# STM32F103C8T6_Subentry.net
KiCad netlist of a schematic drawn in Altium Designer
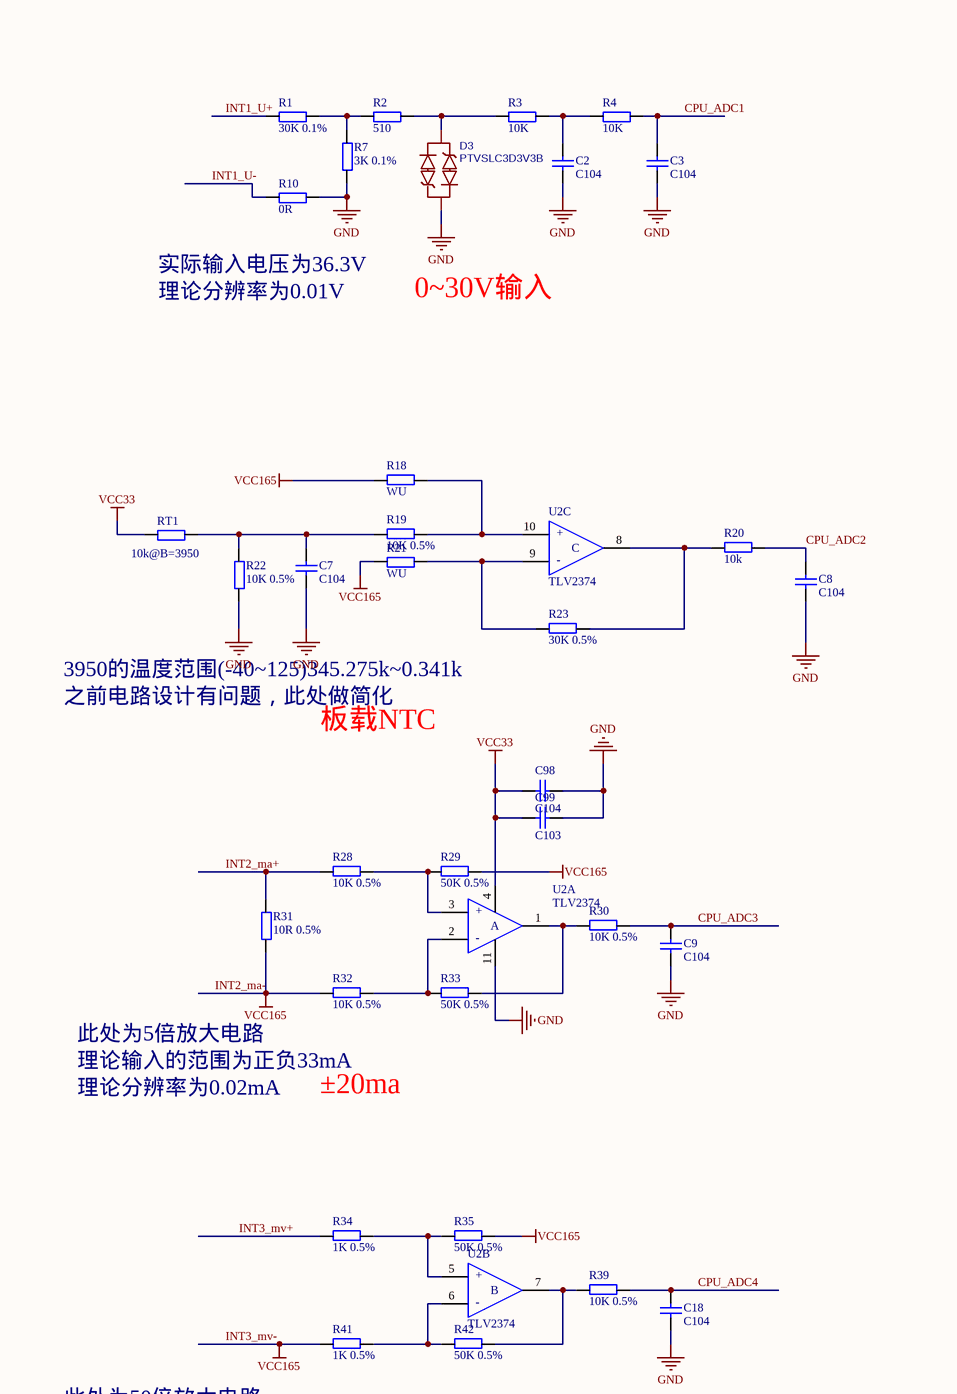
[diagram p0: STM32F103C8T6_Subentry.SchDoc, top left]
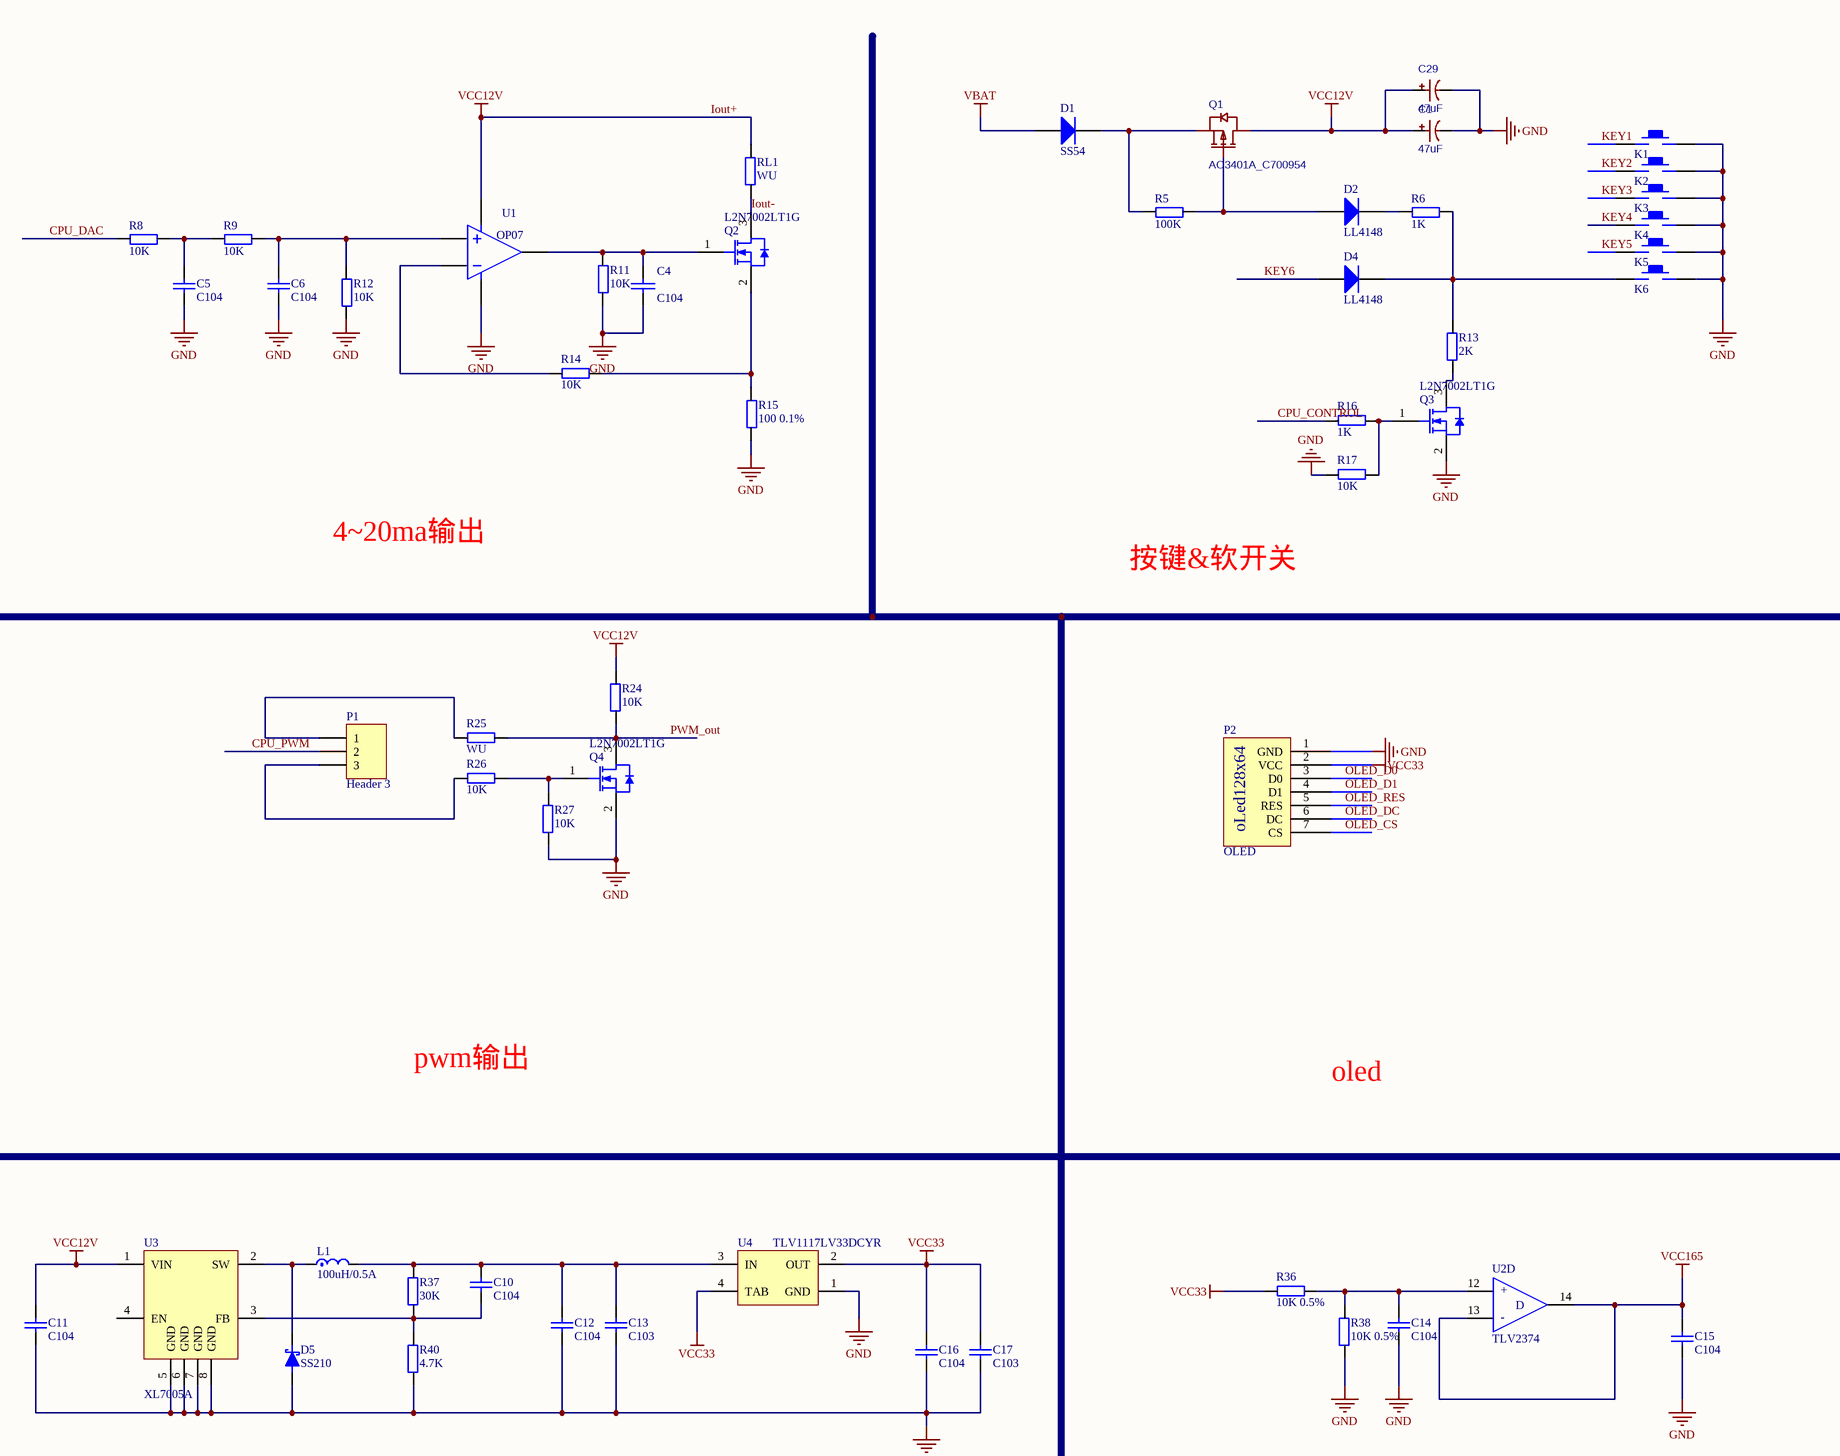
[diagram p1: STM32F103C8T6_Subentry.SchDoc, top right]
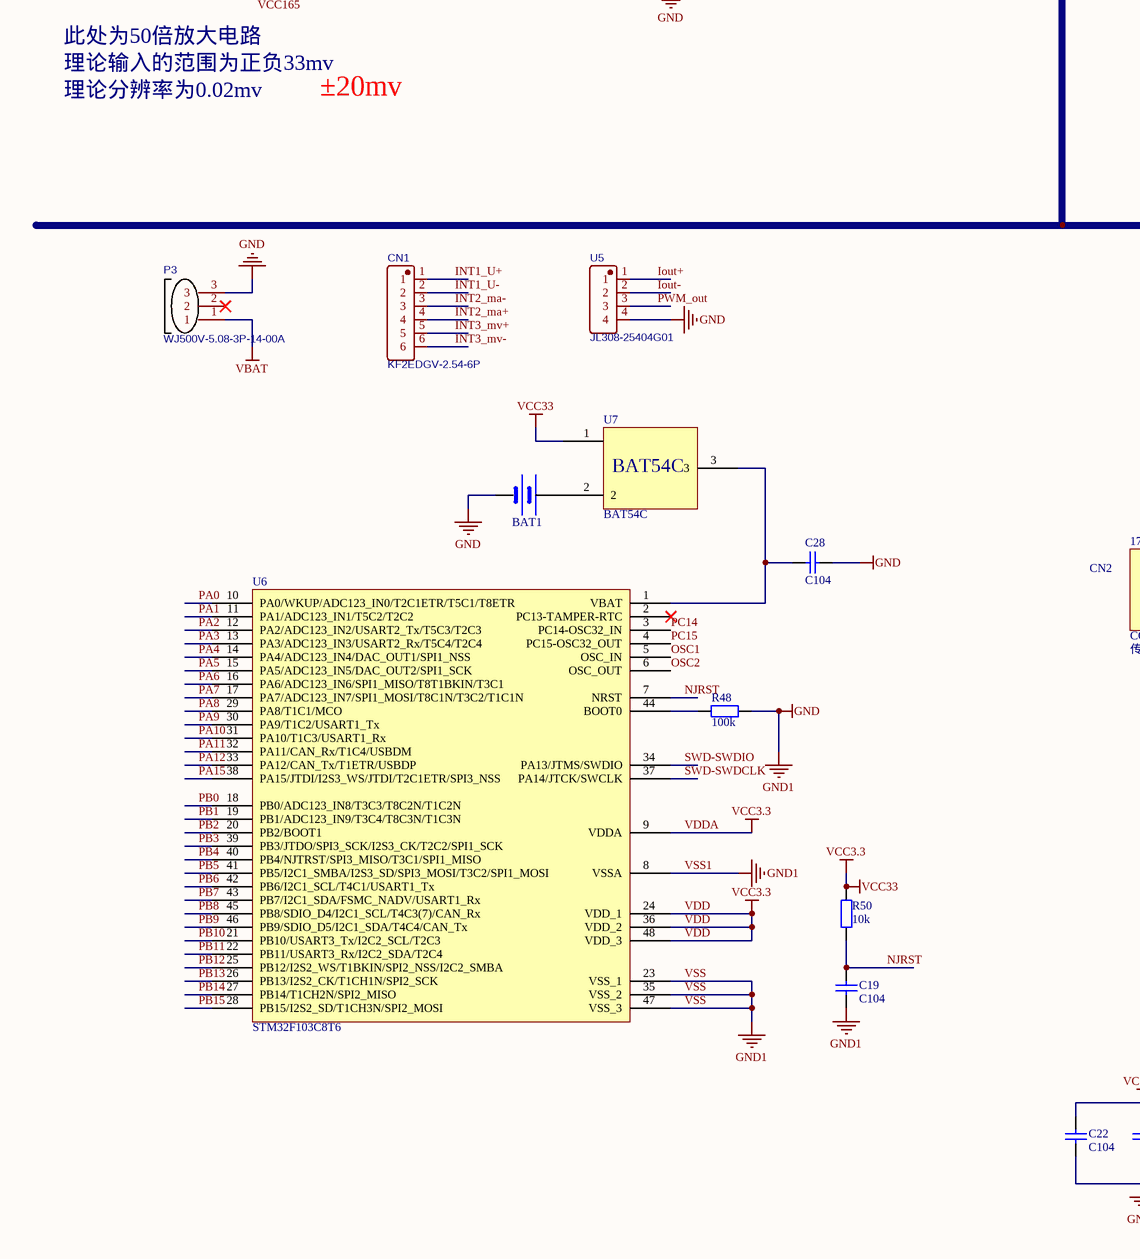
[diagram p2: STM32F103C8T6_Subentry.SchDoc, bottom left]
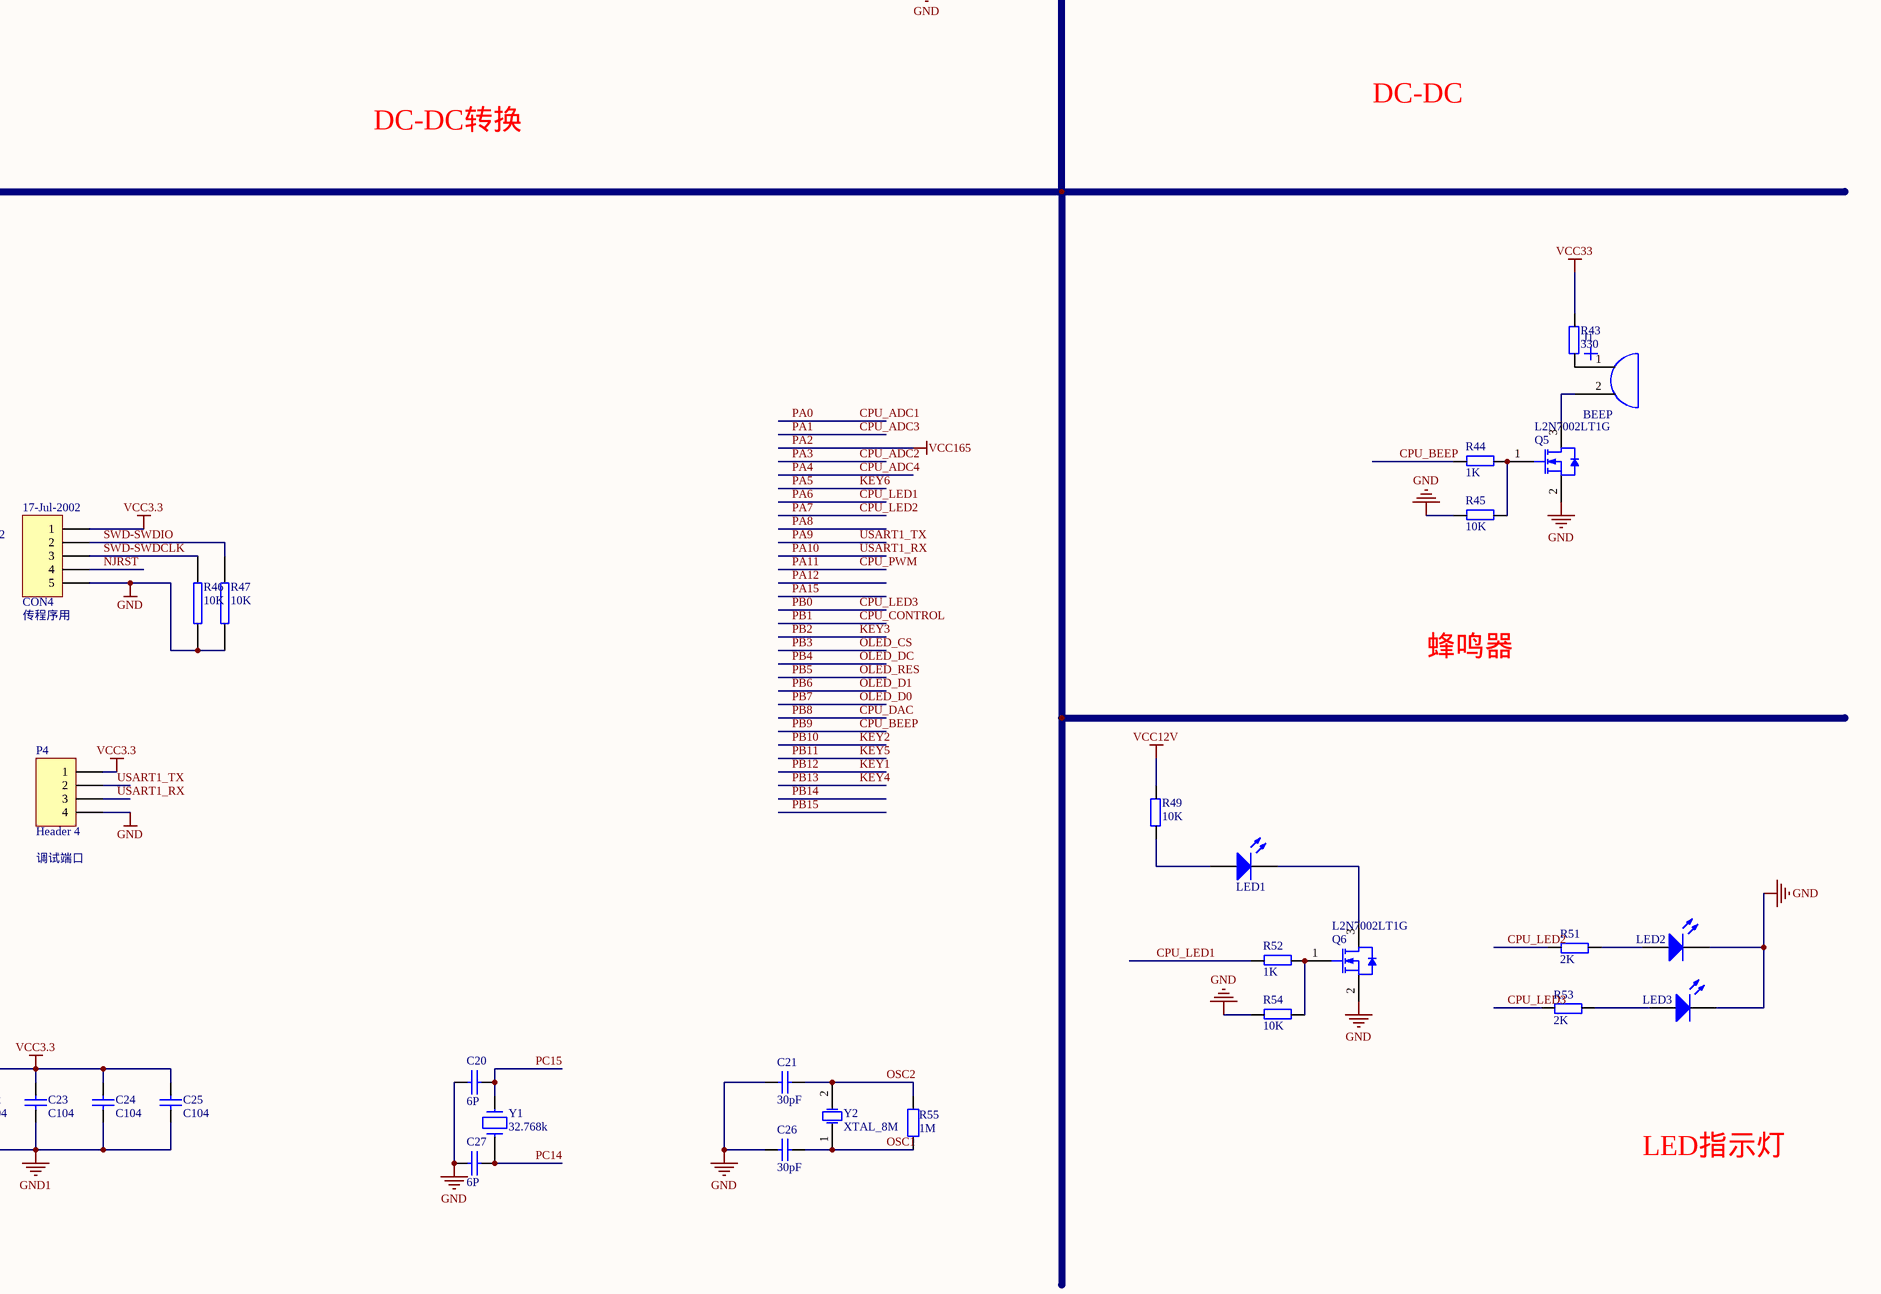
[diagram p3: STM32F103C8T6_Subentry.SchDoc, bottom right]

(export (version "E")
  (design (tool "Eeschema 10.0.6"))
  (components
    (comp (ref "BAT1") (value "BATT") (footprint "CR1220") (libsource (lib "STM32F429_F746") (part "BAT")))
    (comp (ref "C1")
      (value "47uF")
      (footprint "CAP-TH_BD5.0-P2.00-D0.8-FD")
      (fields
        (field (name "BOM_MANUFACTURER PART") "35YXJ47M5X11")
        (field (name "BOM_SUPPLIER PART") "C88761")
      )
      (libsource (lib "STM32F103C8T6_Subentry") (part "47uF"))
    )
    (comp (ref "C2")
      (value "C104")
      (footprint "AD_NEW:C0805")
      (description "Capacitor")
      (fields (field (name "PUBLISHER") "Altium Limited"))
      (libsource (lib "Miscellaneous Devices") (part "Cap"))
    )
    (comp (ref "C3")
      (value "C104")
      (footprint "AD_NEW:C0805")
      (description "Capacitor")
      (fields (field (name "PUBLISHER") "Altium Limited"))
      (libsource (lib "Miscellaneous Devices") (part "Cap"))
    )
    (comp (ref "C4")
      (value "C104")
      (footprint "AD_NEW:C0805")
      (description "Capacitor")
      (libsource (lib "*") (part "CAP"))
    )
    (comp (ref "C5")
      (value "C104")
      (footprint "AD_NEW:C0805")
      (description "Capacitor")
      (fields (field (name "PUBLISHER") "Altium Limited"))
      (libsource (lib "Miscellaneous Devices") (part "Cap"))
    )
    (comp (ref "C6")
      (value "C104")
      (footprint "AD_NEW:C0805")
      (description "Capacitor")
      (fields (field (name "PUBLISHER") "Altium Limited"))
      (libsource (lib "Miscellaneous Devices") (part "Cap"))
    )
    (comp (ref "C7")
      (value "C104")
      (footprint "AD_NEW:C0805")
      (description "Capacitor")
      (fields (field (name "PUBLISHER") "Altium Limited"))
      (libsource (lib "Miscellaneous Devices") (part "Cap"))
    )
    (comp (ref "C8")
      (value "C104")
      (footprint "AD_NEW:C0805")
      (description "Capacitor")
      (fields (field (name "PUBLISHER") "Altium Limited"))
      (libsource (lib "Miscellaneous Devices") (part "Cap"))
    )
    (comp (ref "C9")
      (value "C104")
      (footprint "AD_NEW:C0805")
      (description "Capacitor")
      (fields (field (name "PUBLISHER") "Altium Limited"))
      (libsource (lib "Miscellaneous Devices") (part "Cap"))
    )
    (comp (ref "C10")
      (value "C104")
      (footprint "AD_NEW:C0805")
      (description "Capacitor")
      (fields (field (name "PUBLISHER") "Altium Limited"))
      (libsource (lib "Miscellaneous Devices") (part "Cap"))
    )
    (comp (ref "C11")
      (value "C104")
      (footprint "AD_NEW:C0805")
      (description "Capacitor")
      (fields (field (name "PUBLISHER") "Altium Limited"))
      (libsource (lib "Miscellaneous Devices") (part "Cap"))
    )
    (comp (ref "C12")
      (value "C104")
      (footprint "AD_NEW:C0805")
      (description "Capacitor")
      (fields (field (name "PUBLISHER") "Altium Limited"))
      (libsource (lib "Miscellaneous Devices") (part "Cap"))
    )
    (comp (ref "C13")
      (value "C103")
      (footprint "AD_NEW:C0805")
      (description "Capacitor")
      (fields (field (name "PUBLISHER") "Altium Limited"))
      (libsource (lib "Miscellaneous Devices") (part "Cap"))
    )
    (comp (ref "C14")
      (value "C104")
      (footprint "AD_NEW:C0805")
      (description "Capacitor")
      (fields (field (name "PUBLISHER") "Altium Limited"))
      (libsource (lib "Miscellaneous Devices") (part "Cap"))
    )
    (comp (ref "C15")
      (value "C104")
      (footprint "AD_NEW:C0805")
      (description "Capacitor")
      (fields (field (name "PUBLISHER") "Altium Limited"))
      (libsource (lib "Miscellaneous Devices") (part "Cap"))
    )
    (comp (ref "C16")
      (value "C104")
      (footprint "AD_NEW:C0805")
      (description "Capacitor")
      (fields (field (name "PUBLISHER") "Altium Limited"))
      (libsource (lib "Miscellaneous Devices") (part "Cap"))
    )
    (comp (ref "C17")
      (value "C103")
      (footprint "AD_NEW:C0805")
      (description "Capacitor")
      (fields (field (name "PUBLISHER") "Altium Limited"))
      (libsource (lib "Miscellaneous Devices") (part "Cap"))
    )
    (comp (ref "C18")
      (value "C104")
      (footprint "AD_NEW:C0805")
      (description "Capacitor")
      (fields (field (name "PUBLISHER") "Altium Limited"))
      (libsource (lib "Miscellaneous Devices") (part "Cap"))
    )
    (comp (ref "C19")
      (value "C104")
      (footprint "AD_NEW:C0805")
      (description "Capacitor")
      (fields (field (name "PUBLISHER") "Altium Limited"))
      (libsource (lib "Miscellaneous Devices") (part "Cap"))
    )
    (comp (ref "C20")
      (value "6P")
      (footprint "AD_NEW:C0805")
      (description "Capacitor")
      (libsource (lib "") (part "CAP_1"))
    )
    (comp (ref "C21")
      (value "30pF")
      (footprint "AD_NEW:C0805")
      (description "Capacitor")
      (fields (field (name "PUBLISHER") "Altium Limited"))
      (libsource (lib "Miscellaneous Devices") (part "Cap"))
    )
    (comp (ref "C22")
      (value "C104")
      (footprint "AD_NEW:C0805")
      (description "Capacitor")
      (fields (field (name "PUBLISHER") "Altium Limited"))
      (libsource (lib "Miscellaneous Devices") (part "Cap"))
    )
    (comp (ref "C23")
      (value "C104")
      (footprint "AD_NEW:C0805")
      (description "Capacitor")
      (fields (field (name "PUBLISHER") "Altium Limited"))
      (libsource (lib "Miscellaneous Devices") (part "Cap"))
    )
    (comp (ref "C24")
      (value "C104")
      (footprint "AD_NEW:C0805")
      (description "Capacitor")
      (fields (field (name "PUBLISHER") "Altium Limited"))
      (libsource (lib "Miscellaneous Devices") (part "Cap"))
    )
    (comp (ref "C25")
      (value "C104")
      (footprint "AD_NEW:C0805")
      (description "Capacitor")
      (fields (field (name "PUBLISHER") "Altium Limited"))
      (libsource (lib "Miscellaneous Devices") (part "Cap"))
    )
    (comp (ref "C26")
      (value "30pF")
      (footprint "AD_NEW:C0805")
      (description "Capacitor")
      (fields (field (name "PUBLISHER") "Altium Limited"))
      (libsource (lib "Miscellaneous Devices") (part "Cap"))
    )
    (comp (ref "C27")
      (value "6P")
      (footprint "AD_NEW:C0805")
      (description "Capacitor")
      (libsource (lib "") (part "CAP_1"))
    )
    (comp (ref "C28")
      (value "C104")
      (footprint "AD_NEW:C0805")
      (description "Capacitor")
      (fields (field (name "PUBLISHER") "Altium Limited"))
      (libsource (lib "Miscellaneous Devices") (part "Cap"))
    )
    (comp (ref "C29")
      (value "47uF")
      (footprint "CAP-TH_BD5.0-P2.00-D0.8-FD")
      (fields
        (field (name "BOM_MANUFACTURER PART") "35YXJ47M5X11")
        (field (name "BOM_SUPPLIER PART") "C88761")
      )
      (libsource (lib "STM32F103C8T6_Subentry") (part "47uF"))
    )
    (comp (ref "C98")
      (value "C104")
      (footprint "AD_NEW:C0805")
      (description "Capacitor")
      (fields (field (name "PUBLISHER") "Altium Limited"))
      (libsource (lib "Miscellaneous Devices") (part "Cap"))
    )
    (comp (ref "C99")
      (value "C103")
      (footprint "AD_NEW:C0805")
      (description "Capacitor")
      (fields (field (name "PUBLISHER") "Altium Limited"))
      (libsource (lib "Miscellaneous Devices") (part "Cap"))
    )
    (comp (ref "CN1")
      (value "KF2EDGV-2.54-6P")
      (footprint "CONN-TH_6P-P2.54_KF2EDGV-2.54-6P")
      (fields (field (name "BOM_SUPPLIER PART") "C577589") (field (name "CONTRIBUTOR") "LCSC"))
      (libsource (lib "STM32F103C8T6_Subentry") (part "KF2EDGV-2.54-6P"))
    )
    (comp (ref "CN2")
      (value "CON4")
      (footprint "HDR1X5")
      (description "Header, 5-Pin")
      (fields (field (name "LATESTREVISIONDATE") "17-Jul-2002") (field (name "PUBLISHER") "Altium Limited"))
      (libsource (lib "通用接插头符号") (part "Header 5"))
    )
    (comp (ref "D1")
      (value "SS54")
      (footprint "GNN:DIODE-SMB")
      (description "3 Amp General Purpose Rectifier")
      (fields (field (name "PUBLISHER") "Altium Limited"))
      (libsource (lib "Miscellaneous Devices") (part "Diode 1N5404"))
    )
    (comp (ref "D2")
      (value "LL4148")
      (footprint "LL-34_L3.5-W1.5-RD")
      (description "Default Diode")
      (fields (field (name "PUBLISHER") "Altium Limited"))
      (libsource (lib "Miscellaneous Devices") (part "Diode"))
    )
    (comp (ref "D3")
      (value "PTVSLC3D3V3B")
      (footprint "SOD-323_L1.8-W1.3-LS2.5-BI")
      (fields (field (name "BOM_SUPPLIER PART") "C246774") (field (name "CONTRIBUTOR") "LCSC"))
      (libsource (lib "STM32F103C8T6_Subentry") (part "PTVSLC3D3V3B"))
    )
    (comp (ref "D4")
      (value "LL4148")
      (footprint "LL-34_L3.5-W1.5-RD")
      (description "Default Diode")
      (fields (field (name "PUBLISHER") "Altium Limited"))
      (libsource (lib "Miscellaneous Devices") (part "Diode"))
    )
    (comp (ref "D5") (value "SS210") (footprint "SMA") (libsource (lib "BB4805S") (part "DIODE SCHOTTKY")))
    (comp (ref "J1")
      (value "BEEP")
      (footprint "GNN:Beep")
      (description "蜂鸣器")
      (libsource (lib "GNN") (part "BEEP"))
    )
    (comp (ref "K1")
      (value "KEY_M")
      (footprint "K0.25")
      (libsource (lib "WarShip V3 STM32103封装库") (part "KEY_M"))
    )
    (comp (ref "K2")
      (value "KEY_M")
      (footprint "K0.25")
      (libsource (lib "WarShip V3 STM32103封装库") (part "KEY_M"))
    )
    (comp (ref "K3")
      (value "KEY_M")
      (footprint "K0.25")
      (libsource (lib "WarShip V3 STM32103封装库") (part "KEY_M"))
    )
    (comp (ref "K4")
      (value "KEY_M")
      (footprint "K0.25")
      (libsource (lib "WarShip V3 STM32103封装库") (part "KEY_M"))
    )
    (comp (ref "K5")
      (value "KEY_M")
      (footprint "K0.25")
      (libsource (lib "WarShip V3 STM32103封装库") (part "KEY_M"))
    )
    (comp (ref "K6") (value "KEY_M") (footprint "K0.25") (libsource (lib "") (part "KEY_M_1")))
    (comp (ref "L1") (value "100uH/0.5A") (footprint "L0630") (libsource (lib "BB4805S") (part "INDUTOR")))
    (comp (ref "LED1")
      (value "LED")
      (footprint "LED-0603 - duplicate")
      (description "白色贴片指示灯")
      (fields (field (name "PUBLISHER") "Altium Limited"))
      (libsource (lib "MySchlib1") (part "LED"))
    )
    (comp (ref "LED2")
      (value "LED")
      (footprint "LED-0603 - duplicate")
      (description "白色贴片指示灯")
      (fields (field (name "PUBLISHER") "Altium Limited"))
      (libsource (lib "MySchlib1") (part "LED"))
    )
    (comp (ref "LED3")
      (value "LED")
      (footprint "LED-0603 - duplicate")
      (description "白色贴片指示灯")
      (fields (field (name "PUBLISHER") "Altium Limited"))
      (libsource (lib "MySchlib1") (part "LED"))
    )
    (comp (ref "P1")
      (value "Header 3")
      (footprint "HDR1X3")
      (description "Header, 3-Pin")
      (fields (field (name "PUBLISHER") "Altium Limited"))
      (libsource (lib "Miscellaneous Connectors") (part "Header 3"))
    )
    (comp (ref "P2") (value "OLED") (footprint "OLED") (libsource (lib "Schlib1") (part "OLED")))
    (comp (ref "P3")
      (value "WJ500V-5.08-3P-14-00A")
      (footprint "CONN-TH_3P-P5.00_WJ500V-5.08-3P")
      (fields (field (name "BOM_SUPPLIER PART") "C72334"))
      (libsource (lib "STM32F103C8T6_Subentry") (part "WJ500V-5.08-3P-14-00A"))
    )
    (comp (ref "P4")
      (value "Header 4")
      (footprint "HDR1X4")
      (description "Header, 4-Pin")
      (fields (field (name "PUBLISHER") "Altium Limited"))
      (libsource (lib "Miscellaneous Connectors") (part "Header 4"))
    )
    (comp (ref "Q1")
      (value "AO3401A_C700954")
      (footprint "SOT-23")
      (fields
        (field (name "BOM_SUPPLIER PART") "C700954")
        (field (name "BOM_MANUFACTURER PART") "AO3401A")
        (field (name "CONTRIBUTOR") "LCSC")
      )
      (libsource (lib "STM32F103C8T6_Subentry") (part "AO3401A_C700954"))
    )
    (comp (ref "Q2")
      (value "L2N7002LT1G")
      (footprint "SOT-23")
      (description "N-channel Enhancement Mode Field-effect Transistor")
      (fields (field (name "PUBLISHER") "Altium Limited"))
      (libsource (lib "Philips Discrete MOSFET - Low Power") (part "2N7002"))
    )
    (comp (ref "Q3")
      (value "L2N7002LT1G")
      (footprint "SOT-23")
      (description "N-channel Enhancement Mode Field-effect Transistor")
      (fields (field (name "PUBLISHER") "Altium Limited"))
      (libsource (lib "Philips Discrete MOSFET - Low Power") (part "2N7002"))
    )
    (comp (ref "Q4")
      (value "L2N7002LT1G")
      (footprint "SOT-23")
      (description "N-channel Enhancement Mode Field-effect Transistor")
      (fields (field (name "PUBLISHER") "Altium Limited"))
      (libsource (lib "Philips Discrete MOSFET - Low Power") (part "2N7002"))
    )
    (comp (ref "Q5")
      (value "L2N7002LT1G")
      (footprint "SOT-23")
      (description "N-channel Enhancement Mode Field-effect Transistor")
      (fields (field (name "PUBLISHER") "Altium Limited"))
      (libsource (lib "Philips Discrete MOSFET - Low Power") (part "2N7002"))
    )
    (comp (ref "Q6")
      (value "L2N7002LT1G")
      (footprint "SOT-23")
      (description "N-channel Enhancement Mode Field-effect Transistor")
      (fields (field (name "PUBLISHER") "Altium Limited"))
      (libsource (lib "Philips Discrete MOSFET - Low Power") (part "2N7002"))
    )
    (comp (ref "R1")
      (value "30K 0.1%")
      (footprint "AD_NEW:R1206")
      (description "R202-0603")
      (libsource (lib "MySchlib1") (part "R"))
    )
    (comp (ref "R2")
      (value "510")
      (footprint "AD_NEW:R0805")
      (description "R202-0603")
      (libsource (lib "MySchlib1") (part "R"))
    )
    (comp (ref "R3")
      (value "10K")
      (footprint "AD_NEW:R0805")
      (description "R202-0603")
      (libsource (lib "MySchlib1") (part "R"))
    )
    (comp (ref "R4")
      (value "10K")
      (footprint "AD_NEW:R0805")
      (description "R202-0603")
      (libsource (lib "MySchlib1") (part "R"))
    )
    (comp (ref "R5")
      (value "100K")
      (footprint "AD_NEW:R0805")
      (description "电阻")
      (libsource (lib "GNN") (part "RES"))
    )
    (comp (ref "R6")
      (value "1K")
      (footprint "AD_NEW:R0805")
      (description "R202-0603")
      (libsource (lib "MySchlib1") (part "R"))
    )
    (comp (ref "R7")
      (value "3K 0.1%")
      (footprint "AD_NEW:R1206")
      (description "R202-0603")
      (libsource (lib "MySchlib1") (part "R"))
    )
    (comp (ref "R8")
      (value "10K")
      (footprint "AD_NEW:R0805")
      (description "R202-0603")
      (libsource (lib "MySchlib1") (part "R"))
    )
    (comp (ref "R9")
      (value "10K")
      (footprint "AD_NEW:R0805")
      (description "R202-0603")
      (libsource (lib "MySchlib1") (part "R"))
    )
    (comp (ref "R10")
      (value "0R")
      (footprint "AD_NEW:R1206")
      (description "R202-0603")
      (libsource (lib "MySchlib1") (part "R"))
    )
    (comp (ref "R11")
      (value "10K")
      (footprint "AD_NEW:R0805")
      (description "R202-0603")
      (libsource (lib "MySchlib1") (part "R"))
    )
    (comp (ref "R12")
      (value "10K")
      (footprint "AD_NEW:R0805")
      (description "R202-0603")
      (libsource (lib "MySchlib1") (part "R"))
    )
    (comp (ref "R13")
      (value "2K")
      (footprint "AD_NEW:R0805")
      (description "R202-0603")
      (libsource (lib "MySchlib1") (part "R"))
    )
    (comp (ref "R14")
      (value "10K")
      (footprint "AD_NEW:R0805")
      (description "R202-0603")
      (libsource (lib "MySchlib1") (part "R"))
    )
    (comp (ref "R15")
      (value "100 0.1%")
      (footprint "AD_NEW:R0805")
      (description "R202-0603")
      (libsource (lib "MySchlib1") (part "R"))
    )
    (comp (ref "R16")
      (value "1K")
      (footprint "AD_NEW:R0805")
      (description "R202-0603")
      (libsource (lib "MySchlib1") (part "R"))
    )
    (comp (ref "R17")
      (value "10K")
      (footprint "AD_NEW:R0805")
      (description "R202-0603")
      (libsource (lib "MySchlib1") (part "R"))
    )
    (comp (ref "R18")
      (value "WU")
      (footprint "AD_NEW:R0805")
      (description "R202-0603")
      (libsource (lib "MySchlib1") (part "R"))
    )
    (comp (ref "R19")
      (value "10K 0.5%")
      (footprint "AD_NEW:R0805")
      (description "R202-0603")
      (libsource (lib "MySchlib1") (part "R"))
    )
    (comp (ref "R20")
      (value "10k")
      (footprint "AD_NEW:R0805")
      (description "R202-0603")
      (libsource (lib "MySchlib1") (part "R"))
    )
    (comp (ref "R21")
      (value "WU")
      (footprint "AD_NEW:R0805")
      (description "R202-0603")
      (libsource (lib "MySchlib1") (part "R"))
    )
    (comp (ref "R22")
      (value "10K 0.5%")
      (footprint "AD_NEW:R0805")
      (description "R202-0603")
      (libsource (lib "MySchlib1") (part "R"))
    )
    (comp (ref "R23")
      (value "30K 0.5%")
      (footprint "AD_NEW:R0805")
      (description "R202-0603")
      (libsource (lib "MySchlib1") (part "R"))
    )
    (comp (ref "R24")
      (value "10K")
      (footprint "AD_NEW:R0805")
      (description "R202-0603")
      (libsource (lib "MySchlib1") (part "R"))
    )
    (comp (ref "R25")
      (value "WU")
      (footprint "AD_NEW:R0805")
      (description "R202-0603")
      (libsource (lib "MySchlib1") (part "R"))
    )
    (comp (ref "R26")
      (value "10K")
      (footprint "AD_NEW:R0805")
      (description "R202-0603")
      (libsource (lib "MySchlib1") (part "R"))
    )
    (comp (ref "R27")
      (value "10K")
      (footprint "AD_NEW:R0805")
      (description "R202-0603")
      (libsource (lib "MySchlib1") (part "R"))
    )
    (comp (ref "R28")
      (value "10K 0.5%")
      (footprint "AD_NEW:R0805")
      (description "R202-0603")
      (libsource (lib "MySchlib1") (part "R"))
    )
    (comp (ref "R29")
      (value "50K 0.5%")
      (footprint "AD_NEW:R0805")
      (description "R202-0603")
      (libsource (lib "MySchlib1") (part "R"))
    )
    (comp (ref "R30")
      (value "10K 0.5%")
      (footprint "AD_NEW:R0805")
      (description "R202-0603")
      (libsource (lib "MySchlib1") (part "R"))
    )
    (comp (ref "R31")
      (value "10R 0.5%")
      (footprint "AD_NEW:R0805")
      (description "R202-0603")
      (libsource (lib "MySchlib1") (part "R"))
    )
    (comp (ref "R32")
      (value "10K 0.5%")
      (footprint "AD_NEW:R0805")
      (description "R202-0603")
      (libsource (lib "MySchlib1") (part "R"))
    )
    (comp (ref "R33")
      (value "50K 0.5%")
      (footprint "AD_NEW:R0805")
      (description "R202-0603")
      (libsource (lib "MySchlib1") (part "R"))
    )
    (comp (ref "R34")
      (value "1K 0.5%")
      (footprint "AD_NEW:R0805")
      (description "R202-0603")
      (libsource (lib "MySchlib1") (part "R"))
    )
    (comp (ref "R35")
      (value "50K 0.5%")
      (footprint "AD_NEW:R0805")
      (description "R202-0603")
      (libsource (lib "MySchlib1") (part "R"))
    )
    (comp (ref "R36")
      (value "10K 0.5%")
      (footprint "AD_NEW:R0805")
      (description "R202-0603")
      (libsource (lib "MySchlib1") (part "R"))
    )
    (comp (ref "R37")
      (value "30K")
      (footprint "AD_NEW:R0805")
      (description "R202-0603")
      (libsource (lib "MySchlib1") (part "R"))
    )
    (comp (ref "R38")
      (value "10K 0.5%")
      (footprint "AD_NEW:R0805")
      (description "R202-0603")
      (libsource (lib "MySchlib1") (part "R"))
    )
    (comp (ref "R39")
      (value "10K 0.5%")
      (footprint "AD_NEW:R0805")
      (description "R202-0603")
      (libsource (lib "MySchlib1") (part "R"))
    )
    (comp (ref "R40")
      (value "4.7K")
      (footprint "AD_NEW:R0805")
      (description "R202-0603")
      (libsource (lib "MySchlib1") (part "R"))
    )
    (comp (ref "R41")
      (value "1K 0.5%")
      (footprint "AD_NEW:R0805")
      (description "R202-0603")
      (libsource (lib "MySchlib1") (part "R"))
    )
    (comp (ref "R42")
      (value "50K 0.5%")
      (footprint "AD_NEW:R0805")
      (description "R202-0603")
      (libsource (lib "MySchlib1") (part "R"))
    )
    (comp (ref "R43")
      (value "330")
      (footprint "AD_NEW:R0805")
      (description "R202-0603")
      (libsource (lib "MySchlib1") (part "R"))
    )
    (comp (ref "R44")
      (value "1K")
      (footprint "AD_NEW:R0805")
      (description "R202-0603")
      (libsource (lib "MySchlib1") (part "R"))
    )
    (comp (ref "R45")
      (value "10K")
      (footprint "AD_NEW:R0805")
      (description "R202-0603")
      (libsource (lib "MySchlib1") (part "R"))
    )
    (comp (ref "R46") (value "10K") (footprint "AD_NEW:R0805") (libsource (lib "*") (part "RES2")))
    (comp (ref "R47") (value "10K") (footprint "AD_NEW:R0805") (libsource (lib "*") (part "RES2")))
    (comp (ref "R48")
      (value "100k")
      (footprint "AD_NEW:R0805")
      (description "Resistor")
      (fields (field (name "PUBLISHER") "Altium Limited"))
      (libsource (lib "Miscellaneous Devices") (part "Res2"))
    )
    (comp (ref "R49")
      (value "10K")
      (footprint "AD_NEW:R0805")
      (description "R202-0603")
      (libsource (lib "MySchlib1") (part "R"))
    )
    (comp (ref "R50")
      (value "10k")
      (footprint "AD_NEW:R0805")
      (description "Resistor")
      (fields (field (name "PUBLISHER") "Altium Limited"))
      (libsource (lib "") (part "Res2_1"))
    )
    (comp (ref "R51")
      (value "2K")
      (footprint "AD_NEW:R0805")
      (description "R202-0603")
      (libsource (lib "MySchlib1") (part "R"))
    )
    (comp (ref "R52")
      (value "1K")
      (footprint "AD_NEW:R0805")
      (description "R202-0603")
      (libsource (lib "MySchlib1") (part "R"))
    )
    (comp (ref "R53")
      (value "2K")
      (footprint "AD_NEW:R0805")
      (description "R202-0603")
      (libsource (lib "MySchlib1") (part "R"))
    )
    (comp (ref "R54")
      (value "10K")
      (footprint "AD_NEW:R0805")
      (description "R202-0603")
      (libsource (lib "MySchlib1") (part "R"))
    )
    (comp (ref "R55")
      (value "1M")
      (footprint "AD_NEW:R0805")
      (description "Resistor")
      (fields (field (name "PUBLISHER") "Altium Limited"))
      (libsource (lib "") (part "Res2_1"))
    )
    (comp (ref "RL1")
      (value "WU")
      (footprint "AD_NEW:R1206")
      (description "R202-0603")
      (libsource (lib "MySchlib1") (part "R"))
    )
    (comp (ref "RT1")
      (value "10k@B=3950")
      (footprint "AD_NEW:R0603")
      (description "R202-0603")
      (libsource (lib "MySchlib1") (part "R"))
    )
    (comp (ref "U1") (value "OP07") (footprint "SOP8") (libsource (lib "*") (part "OP07C")))
    (comp (ref "U2") (value "TLV2374") (footprint "SOP14") (libsource (lib "BB4805S") (part "TLV2374")))
    (comp (ref "U3")
      (value "XL7005A")
      (footprint "SOP8")
      (description "step dowm DC/DC")
      (libsource (lib "BB4805S") (part "XL7005A"))
    )
    (comp (ref "U4")
      (value "TLV1117LV33DCYR")
      (footprint "SOT-223")
      (description "800mA Low-Dropout Linear Regulator, 4-pin SOT-223, Pb-Free")
      (fields
        (field (name "PARTNUMBER") "LM1117IMPX-3.3/NOPB")
        (field (name "MANUFACTURER") "National Semiconductor")
        (field (name "PUBLISHER") "Altium Limited")
      )
      (libsource (lib "NSC LDO") (part "LM1117IMPX-3.3/NOPB"))
    )
    (comp (ref "U5")
      (value "JL308-25404G01")
      (footprint "CONN-TH_4P-P2.54_JILN_JL308-25404G01")
      (fields (field (name "BOM_SUPPLIER PART") "C2922599") (field (name "CONTRIBUTOR") "LCSC"))
      (libsource (lib "STM32F103C8T6_Subentry") (part "JL308-25404G01"))
    )
    (comp (ref "U6")
      (value "STM32F103C8T6")
      (footprint "LQFP48_L")
      (description "STM32单片机48引脚")
      (libsource (lib "hrQQJLY00014-1-16-06-06") (part "STM32F103C"))
    )
    (comp (ref "U7") (value "BAT54C") (footprint "GNN:SOT-23") (libsource (lib "GNN") (part "BAT54C")))
    (comp (ref "Y1")
      (value "32.768k")
      (footprint "XTAL32")
      (description "Crystal")
      (libsource (lib "*") (part "CRYSTAL"))
    )
    (comp (ref "Y2")
      (value "XTAL_8M")
      (footprint "XTAL_US")
      (description "Crystal Oscillator")
      (fields (field (name "PUBLISHER") "Altium Limited"))
      (libsource (lib "Miscellaneous Devices") (part "XTAL"))
    )
  )
  (nets
    (net (code "1") (name "/CPU_ADC1") (class "Default")
      (node (ref "C3") (pin "2") (pinfunction "2_2") (pintype "passive"))
      (node (ref "R4") (pin "2") (pintype "passive"))
      (node (ref "U6") (pin "10") (pinfunction "PA0/WKUP/ADC123_IN0/T2C1ETR/T5C1/T8ETR_10") (pintype "passive"))
    )
    (net (code "2") (name "/CPU_ADC2") (class "Default")
      (node (ref "C8") (pin "2") (pinfunction "2_2") (pintype "passive"))
      (node (ref "R20") (pin "1") (pintype "passive"))
      (node (ref "U6") (pin "13") (pinfunction "PA3/ADC123_IN3/USART2_Rx/T5C4/T2C4_13") (pintype "passive"))
    )
    (net (code "3") (name "/CPU_ADC3") (class "Default")
      (node (ref "C9") (pin "2") (pinfunction "2_2") (pintype "passive"))
      (node (ref "R30") (pin "1") (pintype "passive"))
      (node (ref "U6") (pin "11") (pinfunction "PA1/ADC123_IN1/T5C2/T2C2_11") (pintype "passive"))
    )
    (net (code "4") (name "/CPU_ADC4") (class "Default")
      (node (ref "C18") (pin "2") (pinfunction "2_2") (pintype "passive"))
      (node (ref "R39") (pin "1") (pintype "passive"))
      (node (ref "U6") (pin "14") (pinfunction "PA4/ADC123_IN4/DAC_OUT1/SPI1_NSS_14") (pintype "passive"))
    )
    (net (code "5") (name "/CPU_BEEP") (class "Default")
      (node (ref "R44") (pin "2") (pintype "passive"))
      (node (ref "U6") (pin "46") (pinfunction "PB9/SDIO_D5/I2C1_SDA/T4C4/CAN_Tx_46") (pintype "passive"))
    )
    (net (code "6") (name "/CPU_CONTROL") (class "Default")
      (node (ref "R16") (pin "2") (pintype "passive"))
      (node (ref "U6") (pin "19") (pinfunction "PB1/ADC123_IN9/T3C4/T8C3N/T1C3N_19") (pintype "passive"))
    )
    (net (code "7") (name "/CPU_DAC") (class "Default")
      (node (ref "R8") (pin "1") (pintype "passive"))
      (node (ref "U6") (pin "45") (pinfunction "PB8/SDIO_D4/I2C1_SCL/T4C3(7)/CAN_Rx_45") (pintype "passive"))
    )
    (net (code "8") (name "/CPU_LED1") (class "Default")
      (node (ref "R52") (pin "2") (pintype "passive"))
      (node (ref "U6") (pin "16") (pinfunction "PA6/ADC123_IN6/SPI1_MISO/T8T1BKIN/T3C1_16") (pintype "passive"))
    )
    (net (code "9") (name "/CPU_LED2") (class "Default")
      (node (ref "R51") (pin "1") (pintype "passive"))
      (node (ref "U6") (pin "17") (pinfunction "PA7/ADC123_IN7/SPI1_MOSI/T8C1N/T3C2/T1C1N_17") (pintype "passive"))
    )
    (net (code "10") (name "/CPU_LED3") (class "Default")
      (node (ref "R53") (pin "1") (pintype "passive"))
      (node (ref "U6") (pin "18") (pinfunction "PB0/ADC123_IN8/T3C3/T8C2N/T1C2N_18") (pintype "passive"))
    )
    (net (code "11") (name "/CPU_PWM") (class "Default")
      (node (ref "P1") (pin "2") (pinfunction "2_2") (pintype "passive"))
      (node (ref "U6") (pin "32") (pinfunction "PA11/CAN_Rx/T1C4/USBDM_32") (pintype "passive"))
    )
    (net (code "12") (name "/INT1_U+") (class "Default")
      (node (ref "CN1") (pin "1") (pinfunction "1_1") (pintype "passive"))
      (node (ref "R1") (pin "1") (pintype "passive"))
    )
    (net (code "13") (name "/INT1_U-") (class "Default")
      (node (ref "CN1") (pin "2") (pinfunction "2_2") (pintype "passive"))
      (node (ref "R10") (pin "1") (pintype "passive"))
    )
    (net (code "14") (name "/INT2_ma+") (class "Default")
      (node (ref "CN1") (pin "4") (pinfunction "4_4") (pintype "passive"))
      (node (ref "R28") (pin "2") (pintype "passive"))
      (node (ref "R31") (pin "2") (pintype "passive"))
    )
    (net (code "15") (name "/INT3_mv+") (class "Default")
      (node (ref "CN1") (pin "5") (pinfunction "5_5") (pintype "passive"))
      (node (ref "R34") (pin "2") (pintype "passive"))
    )
    (net (code "16") (name "/Iout-") (class "Default")
      (node (ref "Q2") (pin "3") (pinfunction "D_3") (pintype "passive"))
      (node (ref "RL1") (pin "2") (pintype "passive"))
      (node (ref "U5") (pin "2") (pinfunction "2_2") (pintype "passive"))
    )
    (net (code "17") (name "/KEY1") (class "Default")
      (node (ref "K1") (pin "2") (pinfunction "2_2") (pintype "passive"))
      (node (ref "U6") (pin "25") (pinfunction "PB12/I2S2_WS/T1BKIN/SPI2_NSS/I2C2_SMBA_25") (pintype "passive"))
    )
    (net (code "18") (name "/KEY2") (class "Default")
      (node (ref "K2") (pin "2") (pinfunction "2_2") (pintype "passive"))
      (node (ref "U6") (pin "21") (pinfunction "PB10/USART3_Tx/I2C2_SCL/T2C3_21") (pintype "passive"))
    )
    (net (code "19") (name "/KEY3") (class "Default")
      (node (ref "K3") (pin "2") (pinfunction "2_2") (pintype "passive"))
      (node (ref "U6") (pin "20") (pinfunction "PB2/BOOT1_20") (pintype "passive"))
    )
    (net (code "20") (name "/KEY4") (class "Default")
      (node (ref "K4") (pin "2") (pinfunction "2_2") (pintype "passive"))
      (node (ref "U6") (pin "26") (pinfunction "PB13/I2S2_CK/T1CH1N/SPI2_SCK_26") (pintype "passive"))
    )
    (net (code "21") (name "/KEY5") (class "Default")
      (node (ref "K5") (pin "2") (pinfunction "2_2") (pintype "passive"))
      (node (ref "U6") (pin "22") (pinfunction "PB11/USART3_Rx/I2C2_SDA/T2C4_22") (pintype "passive"))
    )
    (net (code "22") (name "/KEY6") (class "Default")
      (node (ref "D4") (pin "1") (pinfunction "A_1") (pintype "passive"))
      (node (ref "U6") (pin "15") (pinfunction "PA5/ADC123_IN5/DAC_OUT2/SPI1_SCK_15") (pintype "passive"))
    )
    (net (code "23") (name "/NJRST") (class "Default")
      (node (ref "C19") (pin "2") (pinfunction "2_2") (pintype "passive"))
      (node (ref "CN2") (pin "4") (pinfunction "4_4") (pintype "passive"))
      (node (ref "R50") (pin "1") (pinfunction "1_1") (pintype "passive"))
      (node (ref "U6") (pin "7") (pinfunction "NRST_7") (pintype "passive"))
    )
    (net (code "24") (name "/OLED_CS") (class "Default")
      (node (ref "P2") (pin "7") (pinfunction "CS_7") (pintype "passive"))
      (node (ref "U6") (pin "39") (pinfunction "PB3/JTDO/SPI3_SCK/I2S3_CK/T2C2/SPI1_SCK_39") (pintype "passive"))
    )
    (net (code "25") (name "/OLED_D0") (class "Default")
      (node (ref "P2") (pin "3") (pinfunction "D0_3") (pintype "passive"))
      (node (ref "U6") (pin "43") (pinfunction "PB7/I2C1_SDA/FSMC_NADV/USART1_Rx_43") (pintype "passive"))
    )
    (net (code "26") (name "/OLED_D1") (class "Default")
      (node (ref "P2") (pin "4") (pinfunction "D1_4") (pintype "passive"))
      (node (ref "U6") (pin "42") (pinfunction "PB6/I2C1_SCL/T4C1/USART1_Tx_42") (pintype "passive"))
    )
    (net (code "27") (name "/OLED_DC") (class "Default")
      (node (ref "P2") (pin "6") (pinfunction "DC_6") (pintype "passive"))
      (node (ref "U6") (pin "40") (pinfunction "PB4/NJTRST/SPI3_MISO/T3C1/SPI1_MISO_40") (pintype "passive"))
    )
    (net (code "28") (name "/OLED_RES") (class "Default")
      (node (ref "P2") (pin "5") (pinfunction "RES_5") (pintype "passive"))
      (node (ref "U6") (pin "41") (pinfunction "PB5/I2C1_SMBA/I2S3_SD/SPI3_MOSI/T3C2/SPI1_MOSI_41") (pintype "passive"))
    )
    (net (code "29") (name "/OSC1") (class "Default")
      (node (ref "C26") (pin "1") (pinfunction "1_1") (pintype "passive"))
      (node (ref "R55") (pin "1") (pinfunction "1_1") (pintype "passive"))
      (node (ref "U6") (pin "5") (pinfunction "OSC_IN_5") (pintype "passive"))
      (node (ref "Y2") (pin "1") (pinfunction "OSC1_1") (pintype "passive"))
    )
    (net (code "30") (name "/OSC2") (class "Default")
      (node (ref "C21") (pin "1") (pinfunction "1_1") (pintype "passive"))
      (node (ref "R55") (pin "2") (pinfunction "2_2") (pintype "passive"))
      (node (ref "U6") (pin "6") (pinfunction "OSC_OUT_6") (pintype "passive"))
      (node (ref "Y2") (pin "2") (pinfunction "OSC2_2") (pintype "passive"))
    )
    (net (code "31") (name "/PA8") (class "Default")
      (node (ref "U6") (pin "29") (pinfunction "PA8/T1C1/MCO_29") (pintype "passive"))
    )
    (net (code "32") (name "/PA9") (class "Default")
      (node (ref "P4") (pin "2") (pinfunction "2_2") (pintype "passive"))
      (node (ref "U6") (pin "30") (pinfunction "PA9/T1C2/USART1_Tx_30") (pintype "passive"))
    )
    (net (code "33") (name "/PA10") (class "Default")
      (node (ref "P4") (pin "3") (pinfunction "3_3") (pintype "passive"))
      (node (ref "U6") (pin "31") (pinfunction "PA10/T1C3/USART1_Rx_31") (pintype "passive"))
    )
    (net (code "34") (name "/PA12") (class "Default")
      (node (ref "U6") (pin "33") (pinfunction "PA12/CAN_Tx/T1ETR/USBDP_33") (pintype "passive"))
    )
    (net (code "35") (name "/PA15") (class "Default")
      (node (ref "U6") (pin "38") (pinfunction "PA15/JTDI/I2S3_WS/JTDI/T2C1ETR/SPI3_NSS_38") (pintype "passive"))
    )
    (net (code "36") (name "/PB14") (class "Default")
      (node (ref "U6") (pin "27") (pinfunction "PB14/T1CH2N/SPI2_MISO_27") (pintype "passive"))
    )
    (net (code "37") (name "/PB15") (class "Default")
      (node (ref "U6") (pin "28") (pinfunction "PB15/I2S2_SD/T1CH3N/SPI2_MOSI_28") (pintype "passive"))
    )
    (net (code "38") (name "/PC14") (class "Default")
      (node (ref "C27") (pin "1") (pinfunction "1_1") (pintype "passive"))
      (node (ref "U6") (pin "3") (pinfunction "PC14-OSC32_IN_3") (pintype "passive"))
      (node (ref "Y1") (pin "1") (pinfunction "1_1") (pintype "passive"))
    )
    (net (code "39") (name "/PC15") (class "Default")
      (node (ref "C20") (pin "1") (pinfunction "1_1") (pintype "passive"))
      (node (ref "U6") (pin "4") (pinfunction "PC15-OSC32_OUT_4") (pintype "passive"))
      (node (ref "Y1") (pin "2") (pinfunction "2_2") (pintype "passive"))
    )
    (net (code "40") (name "/PWM_out") (class "Default")
      (node (ref "Q4") (pin "3") (pinfunction "D_3") (pintype "passive"))
      (node (ref "R24") (pin "2") (pintype "passive"))
      (node (ref "R25") (pin "1") (pintype "passive"))
      (node (ref "U5") (pin "3") (pinfunction "3_3") (pintype "passive"))
    )
    (net (code "41") (name "/SWD-SWDCLK") (class "Default")
      (node (ref "CN2") (pin "3") (pinfunction "3_3") (pintype "passive"))
      (node (ref "R46") (pin "2") (pinfunction "2_2") (pintype "passive"))
      (node (ref "U6") (pin "37") (pinfunction "PA14/JTCK/SWCLK_37") (pintype "passive"))
    )
    (net (code "42") (name "/SWD-SWDIO") (class "Default")
      (node (ref "CN2") (pin "2") (pinfunction "2_2") (pintype "passive"))
      (node (ref "R47") (pin "2") (pinfunction "2_2") (pintype "passive"))
      (node (ref "U6") (pin "34") (pinfunction "PA13/JTMS/SWDIO_34") (pintype "passive"))
    )
    (net (code "43") (name "GND") (class "Default")
      (node (ref "BAT1") (pin "2") (pinfunction "GND_2") (pintype "passive"))
      (node (ref "C1") (pin "2") (pinfunction "2_2") (pintype "passive"))
      (node (ref "C11") (pin "1") (pinfunction "1_1") (pintype "passive"))
      (node (ref "C12") (pin "1") (pinfunction "1_1") (pintype "passive"))
      (node (ref "C13") (pin "1") (pinfunction "1_1") (pintype "passive"))
      (node (ref "C14") (pin "1") (pinfunction "1_1") (pintype "passive"))
      (node (ref "C15") (pin "1") (pinfunction "1_1") (pintype "passive"))
      (node (ref "C16") (pin "1") (pinfunction "1_1") (pintype "passive"))
      (node (ref "C17") (pin "1") (pinfunction "1_1") (pintype "passive"))
      (node (ref "C18") (pin "1") (pinfunction "1_1") (pintype "passive"))
      (node (ref "C19") (pin "1") (pinfunction "1_1") (pintype "passive"))
      (node (ref "C2") (pin "1") (pinfunction "1_1") (pintype "passive"))
      (node (ref "C20") (pin "2") (pinfunction "2_2") (pintype "passive"))
      (node (ref "C21") (pin "2") (pinfunction "2_2") (pintype "passive"))
      (node (ref "C22") (pin "1") (pinfunction "1_1") (pintype "passive"))
      (node (ref "C23") (pin "1") (pinfunction "1_1") (pintype "passive"))
      (node (ref "C24") (pin "1") (pinfunction "1_1") (pintype "passive"))
      (node (ref "C25") (pin "1") (pinfunction "1_1") (pintype "passive"))
      (node (ref "C26") (pin "2") (pinfunction "2_2") (pintype "passive"))
      (node (ref "C27") (pin "2") (pinfunction "2_2") (pintype "passive"))
      (node (ref "C28") (pin "1") (pinfunction "1_1") (pintype "passive"))
      (node (ref "C29") (pin "2") (pinfunction "2_2") (pintype "passive"))
      (node (ref "C3") (pin "1") (pinfunction "1_1") (pintype "passive"))
      (node (ref "C4") (pin "2") (pinfunction "2_2") (pintype "passive"))
      (node (ref "C5") (pin "1") (pinfunction "1_1") (pintype "passive"))
      (node (ref "C6") (pin "1") (pinfunction "1_1") (pintype "passive"))
      (node (ref "C7") (pin "1") (pinfunction "1_1") (pintype "passive"))
      (node (ref "C8") (pin "1") (pinfunction "1_1") (pintype "passive"))
      (node (ref "C9") (pin "1") (pinfunction "1_1") (pintype "passive"))
      (node (ref "C98") (pin "1") (pinfunction "1_1") (pintype "passive"))
      (node (ref "C99") (pin "1") (pinfunction "1_1") (pintype "passive"))
      (node (ref "CN2") (pin "5") (pinfunction "5_5") (pintype "passive"))
      (node (ref "D3") (pin "1") (pinfunction "1_1") (pintype "passive"))
      (node (ref "D5") (pin "1") (pinfunction "A_1") (pintype "passive"))
      (node (ref "K1") (pin "1") (pinfunction "1_1") (pintype "passive"))
      (node (ref "K2") (pin "1") (pinfunction "1_1") (pintype "passive"))
      (node (ref "K3") (pin "1") (pinfunction "1_1") (pintype "passive"))
      (node (ref "K4") (pin "1") (pinfunction "1_1") (pintype "passive"))
      (node (ref "K5") (pin "1") (pinfunction "1_1") (pintype "passive"))
      (node (ref "K6") (pin "2") (pinfunction "2_2") (pintype "passive"))
      (node (ref "LED2") (pin "2") (pinfunction "K_2") (pintype "passive"))
      (node (ref "LED3") (pin "2") (pinfunction "K_2") (pintype "passive"))
      (node (ref "P2") (pin "1") (pinfunction "GND_1") (pintype "passive"))
      (node (ref "P3") (pin "3") (pinfunction "3_3") (pintype "passive"))
      (node (ref "P4") (pin "4") (pinfunction "4_4") (pintype "passive"))
      (node (ref "Q3") (pin "2") (pinfunction "S_2") (pintype "passive"))
      (node (ref "Q4") (pin "2") (pinfunction "S_2") (pintype "passive"))
      (node (ref "Q5") (pin "2") (pinfunction "S_2") (pintype "passive"))
      (node (ref "Q6") (pin "2") (pinfunction "S_2") (pintype "passive"))
      (node (ref "R10") (pin "2") (pintype "passive"))
      (node (ref "R11") (pin "1") (pintype "passive"))
      (node (ref "R12") (pin "1") (pintype "passive"))
      (node (ref "R15") (pin "1") (pintype "passive"))
      (node (ref "R17") (pin "2") (pintype "passive"))
      (node (ref "R22") (pin "1") (pintype "passive"))
      (node (ref "R27") (pin "2") (pintype "passive"))
      (node (ref "R38") (pin "2") (pintype "passive"))
      (node (ref "R40") (pin "2") (pintype "passive"))
      (node (ref "R45") (pin "2") (pintype "passive"))
      (node (ref "R46") (pin "1") (pinfunction "1_1") (pintype "passive"))
      (node (ref "R47") (pin "1") (pinfunction "1_1") (pintype "passive"))
      (node (ref "R48") (pin "2") (pinfunction "2_2") (pintype "passive"))
      (node (ref "R54") (pin "2") (pintype "passive"))
      (node (ref "R7") (pin "1") (pintype "passive"))
      (node (ref "U1") (pin "4") (pintype "passive"))
      (node (ref "U2") (pin "11") (pinfunction "GND_11") (pintype "passive"))
      (node (ref "U3") (pin "5") (pinfunction "GND_5") (pintype "passive"))
      (node (ref "U3") (pin "6") (pinfunction "GND_6") (pintype "passive"))
      (node (ref "U3") (pin "7") (pinfunction "GND_7") (pintype "passive"))
      (node (ref "U3") (pin "8") (pinfunction "GND_8") (pintype "passive"))
      (node (ref "U4") (pin "1") (pinfunction "GND_1") (pintype "power_in"))
      (node (ref "U5") (pin "4") (pinfunction "4_4") (pintype "passive"))
      (node (ref "U6") (pin "23") (pinfunction "VSS_1_23") (pintype "passive"))
      (node (ref "U6") (pin "35") (pinfunction "VSS_2_35") (pintype "passive"))
      (node (ref "U6") (pin "47") (pinfunction "VSS_3_47") (pintype "passive"))
      (node (ref "U6") (pin "8") (pinfunction "VSSA_8") (pintype "passive"))
    )
    (net (code "44") (name "Net-(BAT1-VCC)") (class "Default")
      (node (ref "BAT1") (pin "1") (pinfunction "VCC_1") (pintype "passive"))
      (node (ref "U7") (pin "2") (pinfunction "2_2") (pintype "passive"))
    )
    (net (code "45") (name "Net-(C2-Pad2)") (class "Default")
      (node (ref "C2") (pin "2") (pinfunction "2_2") (pintype "passive"))
      (node (ref "R3") (pin "2") (pintype "passive"))
      (node (ref "R4") (pin "1") (pintype "passive"))
    )
    (net (code "46") (name "Net-(C5-Pad2)") (class "Default")
      (node (ref "C5") (pin "2") (pinfunction "2_2") (pintype "passive"))
      (node (ref "R8") (pin "2") (pintype "passive"))
      (node (ref "R9") (pin "1") (pintype "passive"))
    )
    (net (code "47") (name "Net-(C6-Pad2)") (class "Default")
      (node (ref "C6") (pin "2") (pinfunction "2_2") (pintype "passive"))
      (node (ref "R12") (pin "2") (pintype "passive"))
      (node (ref "R9") (pin "2") (pintype "passive"))
      (node (ref "U1") (pin "3") (pintype "passive"))
    )
    (net (code "48") (name "Net-(C7-Pad2)") (class "Default")
      (node (ref "C7") (pin "2") (pinfunction "2_2") (pintype "passive"))
      (node (ref "R19") (pin "2") (pintype "passive"))
      (node (ref "R22") (pin "2") (pintype "passive"))
      (node (ref "RT1") (pin "2") (pintype "passive"))
    )
    (net (code "49") (name "Net-(D1-K)") (class "Default")
      (node (ref "D1") (pin "2") (pinfunction "K_2") (pintype "passive"))
      (node (ref "Q1") (pin "2") (pinfunction "S_2") (pintype "passive"))
      (node (ref "R5") (pin "1") (pintype "passive"))
    )
    (net (code "50") (name "Net-(D2-A)") (class "Default")
      (node (ref "D2") (pin "1") (pinfunction "A_1") (pintype "passive"))
      (node (ref "Q1") (pin "1") (pinfunction "G_1") (pintype "passive"))
      (node (ref "R5") (pin "2") (pintype "passive"))
    )
    (net (code "51") (name "Net-(D2-K)") (class "Default")
      (node (ref "D2") (pin "2") (pinfunction "K_2") (pintype "passive"))
      (node (ref "R6") (pin "1") (pintype "passive"))
    )
    (net (code "52") (name "Net-(D3-Pad2)") (class "Default")
      (node (ref "D3") (pin "2") (pinfunction "2_2") (pintype "passive"))
      (node (ref "R2") (pin "2") (pintype "passive"))
      (node (ref "R3") (pin "1") (pintype "passive"))
    )
    (net (code "53") (name "Net-(D4-K)") (class "Default")
      (node (ref "D4") (pin "2") (pinfunction "K_2") (pintype "passive"))
      (node (ref "K6") (pin "1") (pinfunction "1_1") (pintype "passive"))
      (node (ref "R13") (pin "1") (pintype "passive"))
      (node (ref "R6") (pin "2") (pintype "passive"))
    )
    (net (code "54") (name "Net-(D5-K)") (class "Default")
      (node (ref "D5") (pin "2") (pinfunction "K_2") (pintype "passive"))
      (node (ref "L1") (pin "1") (pinfunction "1_1") (pintype "passive"))
      (node (ref "U3") (pin "2") (pinfunction "SW_2") (pintype "passive"))
    )
    (net (code "55") (name "Net-(J1-0)") (class "Default")
      (node (ref "J1") (pin "1") (pinfunction "0_1") (pintype "passive"))
      (node (ref "R43") (pin "2") (pintype "passive"))
    )
    (net (code "56") (name "Net-(J1-1)") (class "Default")
      (node (ref "J1") (pin "2") (pinfunction "1_2") (pintype "passive"))
      (node (ref "Q5") (pin "3") (pinfunction "D_3") (pintype "passive"))
    )
    (net (code "57") (name "Net-(LED1-A)") (class "Default")
      (node (ref "LED1") (pin "1") (pinfunction "A_1") (pintype "passive"))
      (node (ref "R49") (pin "2") (pintype "passive"))
    )
    (net (code "58") (name "Net-(LED1-K)") (class "Default")
      (node (ref "LED1") (pin "2") (pinfunction "K_2") (pintype "passive"))
      (node (ref "Q6") (pin "3") (pinfunction "D_3") (pintype "passive"))
    )
    (net (code "59") (name "Net-(LED2-A)") (class "Default")
      (node (ref "LED2") (pin "1") (pinfunction "A_1") (pintype "passive"))
      (node (ref "R51") (pin "2") (pintype "passive"))
    )
    (net (code "60") (name "Net-(LED3-A)") (class "Default")
      (node (ref "LED3") (pin "1") (pinfunction "A_1") (pintype "passive"))
      (node (ref "R53") (pin "2") (pintype "passive"))
    )
    (net (code "61") (name "Net-(P1-Pad1)") (class "Default")
      (node (ref "P1") (pin "1") (pinfunction "1_1") (pintype "passive"))
      (node (ref "R25") (pin "2") (pintype "passive"))
    )
    (net (code "62") (name "Net-(P1-Pad3)") (class "Default")
      (node (ref "P1") (pin "3") (pinfunction "3_3") (pintype "passive"))
      (node (ref "R26") (pin "2") (pintype "passive"))
    )
    (net (code "63") (name "Net-(Q2-G)") (class "Default")
      (node (ref "C4") (pin "1") (pinfunction "1_1") (pintype "passive"))
      (node (ref "Q2") (pin "1") (pinfunction "G_1") (pintype "passive"))
      (node (ref "R11") (pin "2") (pintype "passive"))
      (node (ref "U1") (pin "6") (pintype "passive"))
    )
    (net (code "64") (name "Net-(Q2-S)") (class "Default")
      (node (ref "Q2") (pin "2") (pinfunction "S_2") (pintype "passive"))
      (node (ref "R14") (pin "1") (pintype "passive"))
      (node (ref "R15") (pin "2") (pintype "passive"))
    )
    (net (code "65") (name "Net-(Q3-D)") (class "Default")
      (node (ref "Q3") (pin "3") (pinfunction "D_3") (pintype "passive"))
      (node (ref "R13") (pin "2") (pintype "passive"))
    )
    (net (code "66") (name "Net-(Q3-G)") (class "Default")
      (node (ref "Q3") (pin "1") (pinfunction "G_1") (pintype "passive"))
      (node (ref "R16") (pin "1") (pintype "passive"))
      (node (ref "R17") (pin "1") (pintype "passive"))
    )
    (net (code "67") (name "Net-(Q4-G)") (class "Default")
      (node (ref "Q4") (pin "1") (pinfunction "G_1") (pintype "passive"))
      (node (ref "R26") (pin "1") (pintype "passive"))
      (node (ref "R27") (pin "1") (pintype "passive"))
    )
    (net (code "68") (name "Net-(Q5-G)") (class "Default")
      (node (ref "Q5") (pin "1") (pinfunction "G_1") (pintype "passive"))
      (node (ref "R44") (pin "1") (pintype "passive"))
      (node (ref "R45") (pin "1") (pintype "passive"))
    )
    (net (code "69") (name "Net-(Q6-G)") (class "Default")
      (node (ref "Q6") (pin "1") (pinfunction "G_1") (pintype "passive"))
      (node (ref "R52") (pin "1") (pintype "passive"))
      (node (ref "R54") (pin "1") (pintype "passive"))
    )
    (net (code "70") (name "Net-(R1-Pad2)") (class "Default")
      (node (ref "R1") (pin "2") (pintype "passive"))
      (node (ref "R2") (pin "1") (pintype "passive"))
      (node (ref "R7") (pin "2") (pintype "passive"))
    )
    (net (code "71") (name "Net-(R14-Pad2)") (class "Default")
      (node (ref "R14") (pin "2") (pintype "passive"))
      (node (ref "U1") (pin "2") (pintype "passive"))
    )
    (net (code "72") (name "Net-(U2A-1IN+)") (class "Default")
      (node (ref "R28") (pin "1") (pintype "passive"))
      (node (ref "R29") (pin "2") (pintype "passive"))
      (node (ref "U2") (pin "3") (pinfunction "1IN+_3") (pintype "passive"))
    )
    (net (code "73") (name "Net-(U2A-1IN-)") (class "Default")
      (node (ref "R32") (pin "1") (pintype "passive"))
      (node (ref "R33") (pin "2") (pintype "passive"))
      (node (ref "U2") (pin "2") (pinfunction "1IN-_2") (pintype "passive"))
    )
    (net (code "74") (name "Net-(U2A-1OUT)") (class "Default")
      (node (ref "R30") (pin "2") (pintype "passive"))
      (node (ref "R33") (pin "1") (pintype "passive"))
      (node (ref "U2") (pin "1") (pinfunction "1OUT_1") (pintype "passive"))
    )
    (net (code "75") (name "Net-(U2B-2IN+)") (class "Default")
      (node (ref "R34") (pin "1") (pintype "passive"))
      (node (ref "R35") (pin "2") (pintype "passive"))
      (node (ref "U2") (pin "5") (pinfunction "2IN+_5") (pintype "passive"))
    )
    (net (code "76") (name "Net-(U2B-2IN-)") (class "Default")
      (node (ref "R41") (pin "1") (pintype "passive"))
      (node (ref "R42") (pin "2") (pintype "passive"))
      (node (ref "U2") (pin "6") (pinfunction "2IN-_6") (pintype "passive"))
    )
    (net (code "77") (name "Net-(U2B-2OUT)") (class "Default")
      (node (ref "R39") (pin "2") (pintype "passive"))
      (node (ref "R42") (pin "1") (pintype "passive"))
      (node (ref "U2") (pin "7") (pinfunction "2OUT_7") (pintype "passive"))
    )
    (net (code "78") (name "Net-(U2C-3IN+)") (class "Default")
      (node (ref "R18") (pin "1") (pintype "passive"))
      (node (ref "R19") (pin "1") (pintype "passive"))
      (node (ref "U2") (pin "10") (pinfunction "3IN+_10") (pintype "passive"))
    )
    (net (code "79") (name "Net-(U2C-3IN-)") (class "Default")
      (node (ref "R21") (pin "2") (pintype "passive"))
      (node (ref "R23") (pin "2") (pintype "passive"))
      (node (ref "U2") (pin "9") (pinfunction "3IN-_9") (pintype "passive"))
    )
    (net (code "80") (name "Net-(U2C-3OUT)") (class "Default")
      (node (ref "R20") (pin "2") (pintype "passive"))
      (node (ref "R23") (pin "1") (pintype "passive"))
      (node (ref "U2") (pin "8") (pinfunction "3OUT_8") (pintype "passive"))
    )
    (net (code "81") (name "Net-(U2D-4IN+)") (class "Default")
      (node (ref "C14") (pin "2") (pinfunction "2_2") (pintype "passive"))
      (node (ref "R36") (pin "1") (pintype "passive"))
      (node (ref "R38") (pin "1") (pintype "passive"))
      (node (ref "U2") (pin "12") (pinfunction "4IN+_12") (pintype "passive"))
    )
    (net (code "82") (name "Net-(U3-FB)") (class "Default")
      (node (ref "C10") (pin "1") (pinfunction "1_1") (pintype "passive"))
      (node (ref "R37") (pin "2") (pintype "passive"))
      (node (ref "R40") (pin "1") (pintype "passive"))
      (node (ref "U3") (pin "3") (pinfunction "FB_3") (pintype "passive"))
    )
    (net (code "83") (name "Net-(U4-IN)") (class "Default")
      (node (ref "C10") (pin "2") (pinfunction "2_2") (pintype "passive"))
      (node (ref "C12") (pin "2") (pinfunction "2_2") (pintype "passive"))
      (node (ref "C13") (pin "2") (pinfunction "2_2") (pintype "passive"))
      (node (ref "L1") (pin "2") (pinfunction "2_2") (pintype "passive"))
      (node (ref "R37") (pin "1") (pintype "passive"))
      (node (ref "U4") (pin "3") (pinfunction "IN_3") (pintype "power_in"))
    )
    (net (code "84") (name "Net-(U6-BOOT0)") (class "Default")
      (node (ref "R48") (pin "1") (pinfunction "1_1") (pintype "passive"))
      (node (ref "U6") (pin "44") (pinfunction "BOOT0_44") (pintype "passive"))
    )
    (net (code "85") (name "Net-(U6-VBAT)") (class "Default")
      (node (ref "C28") (pin "2") (pinfunction "2_2") (pintype "passive"))
      (node (ref "U6") (pin "1") (pinfunction "VBAT_1") (pintype "passive"))
      (node (ref "U7") (pin "3") (pinfunction "3_3") (pintype "passive"))
    )
    (net (code "86") (name "VBAT") (class "Default")
      (node (ref "D1") (pin "1") (pinfunction "A_1") (pintype "passive"))
      (node (ref "P3") (pin "1") (pinfunction "1_1") (pintype "passive"))
    )
    (net (code "87") (name "VCC3.3") (class "Default")
      (node (ref "C16") (pin "2") (pinfunction "2_2") (pintype "passive"))
      (node (ref "C17") (pin "2") (pinfunction "2_2") (pintype "passive"))
      (node (ref "C22") (pin "2") (pinfunction "2_2") (pintype "passive"))
      (node (ref "C23") (pin "2") (pinfunction "2_2") (pintype "passive"))
      (node (ref "C24") (pin "2") (pinfunction "2_2") (pintype "passive"))
      (node (ref "C25") (pin "2") (pinfunction "2_2") (pintype "passive"))
      (node (ref "C98") (pin "2") (pinfunction "2_2") (pintype "passive"))
      (node (ref "C99") (pin "2") (pinfunction "2_2") (pintype "passive"))
      (node (ref "CN2") (pin "1") (pinfunction "1_1") (pintype "passive"))
      (node (ref "P2") (pin "2") (pinfunction "VCC_2") (pintype "passive"))
      (node (ref "P4") (pin "1") (pinfunction "1_1") (pintype "passive"))
      (node (ref "R36") (pin "2") (pintype "passive"))
      (node (ref "R43") (pin "1") (pintype "passive"))
      (node (ref "R50") (pin "2") (pinfunction "2_2") (pintype "passive"))
      (node (ref "RT1") (pin "1") (pintype "passive"))
      (node (ref "U2") (pin "4") (pinfunction "VCC_4") (pintype "passive"))
      (node (ref "U4") (pin "2") (pinfunction "OUT_2") (pintype "power_in"))
      (node (ref "U4") (pin "4") (pinfunction "TAB_4") (pintype "power_in"))
      (node (ref "U6") (pin "24") (pinfunction "VDD_1_24") (pintype "passive"))
      (node (ref "U6") (pin "36") (pinfunction "VDD_2_36") (pintype "passive"))
      (node (ref "U6") (pin "48") (pinfunction "VDD_3_48") (pintype "passive"))
      (node (ref "U6") (pin "9") (pinfunction "VDDA_9") (pintype "passive"))
      (node (ref "U7") (pin "1") (pintype "passive"))
    )
    (net (code "88") (name "VCC12V") (class "Default")
      (node (ref "C1") (pin "1") (pinfunction "1_1") (pintype "passive"))
      (node (ref "C11") (pin "2") (pinfunction "2_2") (pintype "passive"))
      (node (ref "C29") (pin "1") (pinfunction "1_1") (pintype "passive"))
      (node (ref "Q1") (pin "3") (pinfunction "D_3") (pintype "passive"))
      (node (ref "R24") (pin "1") (pintype "passive"))
      (node (ref "R49") (pin "1") (pintype "passive"))
      (node (ref "RL1") (pin "1") (pintype "passive"))
      (node (ref "U1") (pin "7") (pintype "passive"))
      (node (ref "U3") (pin "1") (pinfunction "VIN_1") (pintype "passive"))
      (node (ref "U5") (pin "1") (pinfunction "1_1") (pintype "passive"))
    )
    (net (code "89") (name "VCC165") (class "Default")
      (node (ref "C15") (pin "2") (pinfunction "2_2") (pintype "passive"))
      (node (ref "CN1") (pin "3") (pinfunction "3_3") (pintype "passive"))
      (node (ref "CN1") (pin "6") (pinfunction "6_6") (pintype "passive"))
      (node (ref "R18") (pin "2") (pintype "passive"))
      (node (ref "R21") (pin "1") (pintype "passive"))
      (node (ref "R29") (pin "1") (pintype "passive"))
      (node (ref "R31") (pin "1") (pintype "passive"))
      (node (ref "R32") (pin "2") (pintype "passive"))
      (node (ref "R35") (pin "1") (pintype "passive"))
      (node (ref "R41") (pin "2") (pintype "passive"))
      (node (ref "U2") (pin "13") (pinfunction "4IN-_13") (pintype "passive"))
      (node (ref "U2") (pin "14") (pinfunction "4OUT_14") (pintype "passive"))
      (node (ref "U6") (pin "12") (pinfunction "PA2/ADC123_IN2/USART2_Tx/T5C3/T2C3_12") (pintype "passive"))
    )
    (net (code "90") (name "unconnected-(P3-Pad2)") (class "Default")
      (node (ref "P3") (pin "2") (pinfunction "2_2") (pintype "passive+no_connect"))
    )
    (net (code "91") (name "unconnected-(U3-EN-Pad4)") (class "Default")
      (node (ref "U3") (pin "4") (pinfunction "EN_4") (pintype "passive"))
    )
    (net (code "92") (name "unconnected-(U6-PC13-TAMPER-RTC-Pad2)") (class "Default")
      (node (ref "U6") (pin "2") (pinfunction "PC13-TAMPER-RTC_2") (pintype "passive+no_connect"))
    )
  )
)
